# Son_BU_V2.net
KiCad netlist of a schematic drawn in Altium Designer
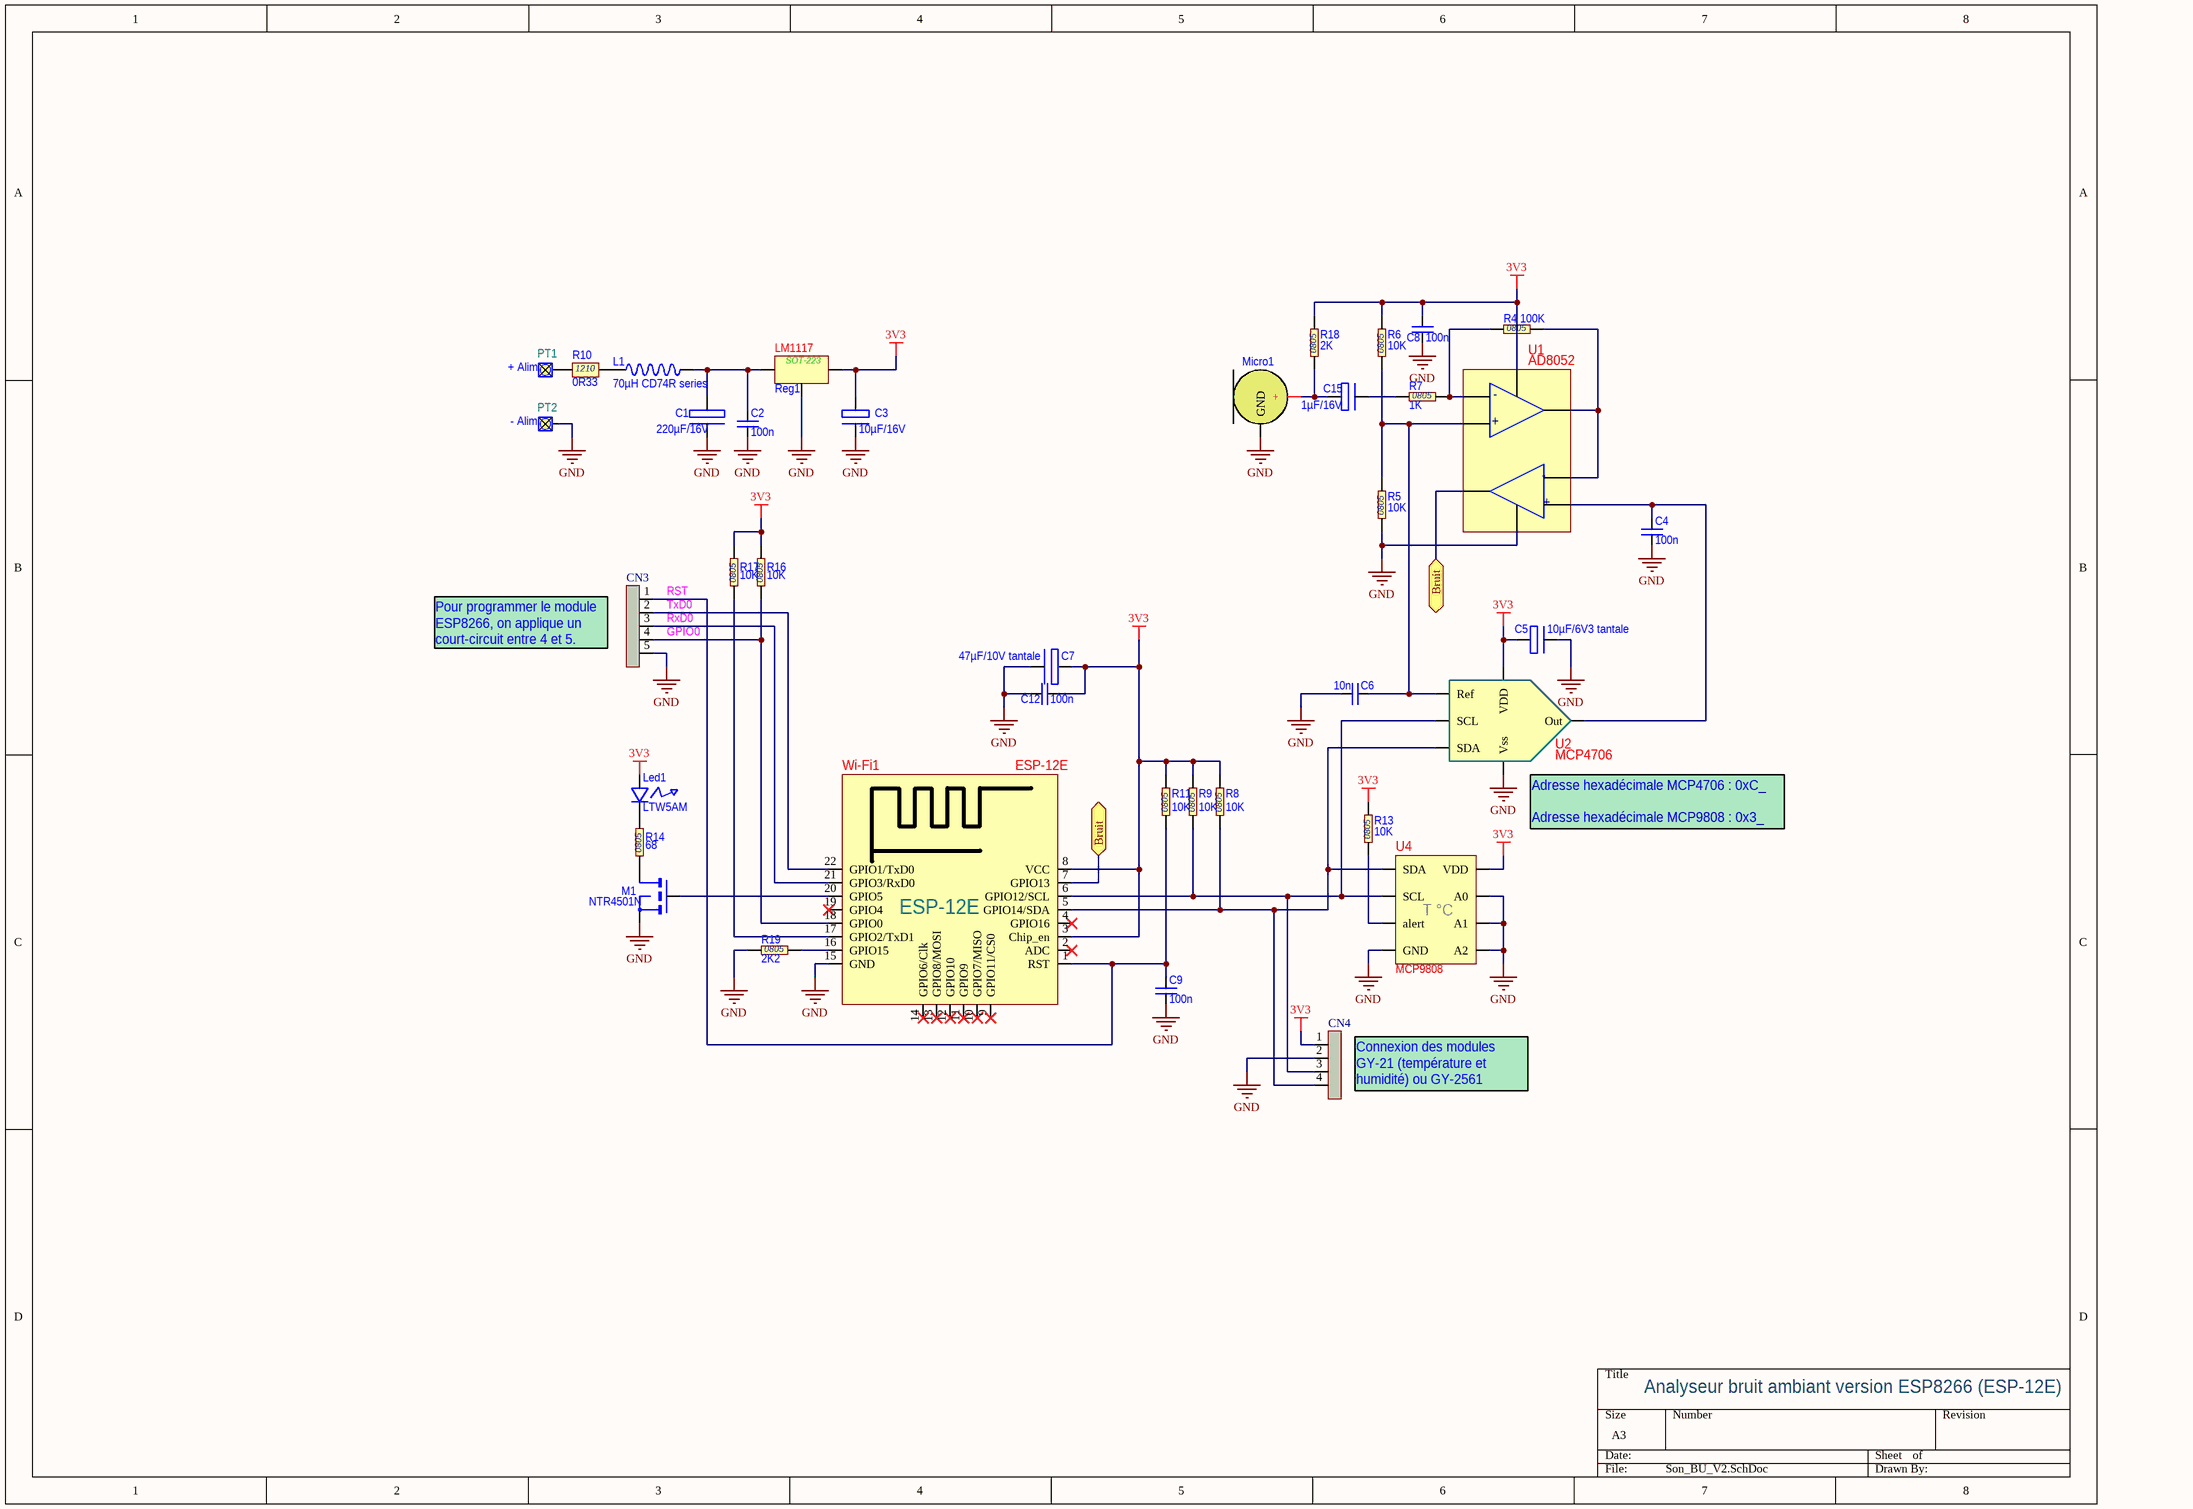
[diagram p0: Son_BU_V2.SchDoc]

(export (version "E")
  (design (tool "Eeschema 10.0.6"))
  (components
    (comp (ref "C1")
      (value "220µF/16V")
      (footprint "7343-31")
      (description "253-5290 case 7343-31")
      (libsource (lib "CMS") (part "tantale 220µF/16V"))
    )
    (comp (ref "C2")
      (value "100n")
      (footprint "0805")
      (description "CMS 0805")
      (libsource (lib "CMS") (part "Cap_CMS_0805"))
    )
    (comp (ref "C3")
      (value "10µF/16V")
      (footprint "Tantale 10µF/16V")
      (description "145-7461 case 3216-18")
      (libsource (lib "CMS") (part "tantale 10µF/16V"))
    )
    (comp (ref "C4")
      (value "100n")
      (footprint "0805")
      (description "CMS 0805")
      (libsource (lib "CMS") (part "Cap_CMS_0805"))
    )
    (comp (ref "C5")
      (value "10µF/6V3 tantale")
      (footprint "Tantale 10µF/6V3")
      (description "175-4041 ou 145-7412 case 3216-18")
      (libsource (lib "CMS") (part "tantale 10µF/6V3"))
    )
    (comp (ref "C6")
      (value "10n")
      (footprint "0805")
      (description "CMS 0805")
      (libsource (lib "CMS") (part "Cap_CMS_0805"))
    )
    (comp (ref "C7")
      (value "47µF/10V tantale")
      (footprint "tantale 47µF/10V")
      (description "175-4168")
      (libsource (lib "CMS") (part "tantale 47µF/10V"))
    )
    (comp (ref "C8")
      (value "100n")
      (footprint "0805")
      (description "CMS 0805")
      (libsource (lib "CMS") (part "Cap_CMS_0805"))
    )
    (comp (ref "C9")
      (value "100n")
      (footprint "0805")
      (description "CMS 0805")
      (libsource (lib "CMS") (part "Cap_CMS_0805"))
    )
    (comp (ref "C12")
      (value "100n")
      (footprint "0805")
      (description "CMS 0805")
      (libsource (lib "CMS") (part "Cap_CMS_0805"))
    )
    (comp (ref "C15")
      (value "1µF/16V")
      (footprint "3216-18")
      (description "145-7406 case 3216-18")
      (libsource (lib "CMS") (part "tantale 1µF/16V"))
    )
    (comp (ref "CN3")
      (value "inch_ligne 1x5")
      (footprint "INCH_1x5_droit")
      (description "Inch_1x5_droit")
      (libsource (lib "Connecteurs Contacts") (part "Inch_1x5_droit"))
    )
    (comp (ref "CN4")
      (value "inch_ligne 1x4")
      (footprint "INCH_1x4_droit")
      (description "Inch_1x4_droit")
      (libsource (lib "Connecteurs Contacts") (part "Inch_1x4_droit"))
    )
    (comp (ref "L1")
      (value "70µH CD74R series")
      (footprint "SELF CD74R")
      (description "SMT CD74R Aliexpress")
      (libsource (lib "CMS") (part "Self CD74R"))
    )
    (comp (ref "Led1")
      (value "LTW5AM")
      (footprint "LTW5AM")
      (description "LED Golden Dragon Plus")
      (libsource (lib "CMS") (part "LTW5AM LED"))
    )
    (comp (ref "M1")
      (value "NTR4501N")
      (footprint "SOT23 (NTR4501)")
      (description "MOSFET canal N")
      (libsource (lib "Transistors Bip Mos IGBT") (part "NTR4501N"))
    )
    (comp (ref "Micro1")
      (value "Electret")
      (footprint "Micro_electret simple")
      (description "Microphone électret")
      (libsource (lib "traversants") (part "Microphone_03"))
    )
    (comp (ref "PT1")
      (value "+ Alim")
      (footprint "Pointe de test")
      (description "pointe de test CI 133-6225")
      (libsource (lib "Connecteurs Contacts") (part "PTEST"))
    )
    (comp (ref "PT2")
      (value "- Alim")
      (footprint "Pointe de test")
      (description "pointe de test CI 133-6225")
      (libsource (lib "Connecteurs Contacts") (part "PTEST"))
    )
    (comp (ref "R4")
      (value "100K")
      (footprint "0805")
      (description "CMS 0805")
      (libsource (lib "") (part "Res CMS 0805_1"))
    )
    (comp (ref "R5")
      (value "10K")
      (footprint "0805")
      (description "CMS 0805")
      (libsource (lib "CMS") (part "Res CMS 0805"))
    )
    (comp (ref "R6")
      (value "10K")
      (footprint "0805")
      (description "CMS 0805")
      (libsource (lib "CMS") (part "Res CMS 0805"))
    )
    (comp (ref "R7")
      (value "1K")
      (footprint "0805")
      (description "CMS 0805")
      (libsource (lib "") (part "Res CMS 0805_1"))
    )
    (comp (ref "R8")
      (value "10K")
      (footprint "0805")
      (description "CMS 0805")
      (libsource (lib "CMS") (part "Res CMS 0805"))
    )
    (comp (ref "R9")
      (value "10K")
      (footprint "0805")
      (description "CMS 0805")
      (libsource (lib "CMS") (part "Res CMS 0805"))
    )
    (comp (ref "R10")
      (value "0R33")
      (footprint "1210")
      (description "CMS 1210")
      (libsource (lib "CMS") (part "Res CMS 1210 ERJ14B"))
    )
    (comp (ref "R11")
      (value "10K")
      (footprint "0805")
      (description "CMS 0805")
      (libsource (lib "CMS") (part "Res CMS 0805"))
    )
    (comp (ref "R13")
      (value "10K")
      (footprint "0805")
      (description "CMS 0805")
      (libsource (lib "CMS") (part "Res CMS 0805"))
    )
    (comp (ref "R14")
      (value "68")
      (footprint "0805")
      (description "CMS 0805")
      (libsource (lib "CMS") (part "Res CMS 0805"))
    )
    (comp (ref "R16")
      (value "10K")
      (footprint "0805")
      (description "CMS 0805")
      (libsource (lib "CMS") (part "Res CMS 0805"))
    )
    (comp (ref "R17")
      (value "10K")
      (footprint "0805")
      (description "CMS 0805")
      (libsource (lib "CMS") (part "Res CMS 0805"))
    )
    (comp (ref "R18")
      (value "2K")
      (footprint "0805")
      (description "CMS 0805")
      (libsource (lib "CMS") (part "Res CMS 0805"))
    )
    (comp (ref "R19")
      (value "2K2")
      (footprint "0805")
      (description "CMS 0805")
      (libsource (lib "") (part "Res CMS 0805_1"))
    )
    (comp (ref "Reg1")
      (value "LM1117")
      (footprint "SOT223")
      (description "Régulateur SOT-223")
      (libsource (lib "Convertisseurs_Régulateurs") (part "LM1117/800mA"))
    )
    (comp (ref "U1")
      (value "AD8052")
      (footprint "SOIC08")
      (description "AOP")
      (libsource (lib "CMS") (part "AD8052"))
    )
    (comp (ref "U2")
      (value "MCP4706")
      (footprint "SOT23-6")
      (description "DAC I2C (RS : 738-7111)")
      (libsource (lib "CMS") (part "MCP4706_1"))
    )
    (comp (ref "U4")
      (value "MCP9808")
      (footprint "MSOP-08")
      (description "Digital temperature Sensor")
      (libsource (lib "CMS") (part "MCP9808"))
    )
    (comp (ref "Wi-Fi1")
      (value "ESP-12E")
      (footprint "ESP-12E")
      (description "ESP-12E module Wi-Fi")
      (libsource (lib "CMS") (part "ESP-12E"))
    )
  )
  (nets
    (net (code "1") (name "/Bruit") (class "Default")
      (node (ref "U1") (pin "7") (pinfunction "out_7") (pintype "passive"))
      (node (ref "Wi-Fi1") (pin "7") (pinfunction "GPIO13_7") (pintype "passive"))
    )
    (net (code "2") (name "/GPIO0") (class "Default")
      (node (ref "CN3") (pin "4") (pintype "passive"))
      (node (ref "R16") (pin "1") (pinfunction "CT1_1") (pintype "passive"))
      (node (ref "Wi-Fi1") (pin "18") (pinfunction "GPIO0_18") (pintype "passive"))
    )
    (net (code "3") (name "/RST") (class "Default")
      (node (ref "C9") (pin "2") (pinfunction "CT2_2") (pintype "passive"))
      (node (ref "CN3") (pin "1") (pintype "passive"))
      (node (ref "R11") (pin "1") (pinfunction "CT1_1") (pintype "passive"))
      (node (ref "Wi-Fi1") (pin "1") (pinfunction "RST_1") (pintype "passive"))
    )
    (net (code "4") (name "/RxD0") (class "Default")
      (node (ref "CN3") (pin "3") (pintype "passive"))
      (node (ref "Wi-Fi1") (pin "21") (pinfunction "GPIO3/RxD0_21") (pintype "passive"))
    )
    (net (code "5") (name "/TxD0") (class "Default")
      (node (ref "CN3") (pin "2") (pintype "passive"))
      (node (ref "Wi-Fi1") (pin "22") (pinfunction "GPIO1/TxD0_22") (pintype "passive"))
    )
    (net (code "6") (name "3V3") (class "Default")
      (node (ref "C12") (pin "2") (pinfunction "CT2_2") (pintype "passive"))
      (node (ref "C3") (pin "1") (pinfunction "V+_1") (pintype "passive"))
      (node (ref "C5") (pin "1") (pinfunction "V+_1") (pintype "passive"))
      (node (ref "C7") (pin "1") (pinfunction "V+_1") (pintype "passive"))
      (node (ref "C8") (pin "2") (pinfunction "CT2_2") (pintype "passive"))
      (node (ref "CN4") (pin "1") (pintype "passive"))
      (node (ref "Led1") (pin "1") (pinfunction "anode_1") (pintype "passive"))
      (node (ref "R11") (pin "2") (pinfunction "CT2_2") (pintype "passive"))
      (node (ref "R13") (pin "2") (pinfunction "CT2_2") (pintype "passive"))
      (node (ref "R16") (pin "2") (pinfunction "CT2_2") (pintype "passive"))
      (node (ref "R17") (pin "2") (pinfunction "CT2_2") (pintype "passive"))
      (node (ref "R18") (pin "2") (pinfunction "CT2_2") (pintype "passive"))
      (node (ref "R6") (pin "2") (pinfunction "CT2_2") (pintype "passive"))
      (node (ref "R8") (pin "2") (pinfunction "CT2_2") (pintype "passive"))
      (node (ref "R9") (pin "2") (pinfunction "CT2_2") (pintype "passive"))
      (node (ref "Reg1") (pin "2") (pinfunction "OUT_2") (pintype "passive"))
      (node (ref "U1") (pin "8") (pinfunction "V+_8") (pintype "passive"))
      (node (ref "U2") (pin "3") (pinfunction "VDD_3") (pintype "passive"))
      (node (ref "U4") (pin "8") (pinfunction "VDD_8") (pintype "passive"))
      (node (ref "Wi-Fi1") (pin "3") (pinfunction "Chip_en_3") (pintype "passive"))
      (node (ref "Wi-Fi1") (pin "8") (pinfunction "VCC_8") (pintype "passive"))
    )
    (net (code "7") (name "GND") (class "Default")
      (node (ref "C1") (pin "2") (pinfunction "V-_2") (pintype "passive"))
      (node (ref "C12") (pin "1") (pinfunction "CT1_1") (pintype "passive"))
      (node (ref "C2") (pin "1") (pinfunction "CT1_1") (pintype "passive"))
      (node (ref "C3") (pin "2") (pinfunction "V-_2") (pintype "passive"))
      (node (ref "C4") (pin "1") (pinfunction "CT1_1") (pintype "passive"))
      (node (ref "C5") (pin "2") (pinfunction "V-_2") (pintype "passive"))
      (node (ref "C6") (pin "2") (pinfunction "CT2_2") (pintype "passive"))
      (node (ref "C7") (pin "2") (pinfunction "V-_2") (pintype "passive"))
      (node (ref "C8") (pin "1") (pinfunction "CT1_1") (pintype "passive"))
      (node (ref "C9") (pin "1") (pinfunction "CT1_1") (pintype "passive"))
      (node (ref "CN3") (pin "5") (pintype "passive"))
      (node (ref "CN4") (pin "2") (pintype "passive"))
      (node (ref "M1") (pin "3") (pinfunction "S_3") (pintype "passive"))
      (node (ref "Micro1") (pin "0") (pinfunction "GND_0") (pintype "passive"))
      (node (ref "PT2") (pin "1") (pinfunction "PIN_1") (pintype "passive"))
      (node (ref "R19") (pin "1") (pinfunction "CT1_1") (pintype "passive"))
      (node (ref "R5") (pin "1") (pinfunction "CT1_1") (pintype "passive"))
      (node (ref "Reg1") (pin "1") (pinfunction "GND_1") (pintype "passive"))
      (node (ref "U1") (pin "4") (pinfunction "V-_4") (pintype "passive"))
      (node (ref "U2") (pin "2") (pinfunction "Vss_2") (pintype "passive"))
      (node (ref "U4") (pin "4") (pinfunction "GND_4") (pintype "passive"))
      (node (ref "U4") (pin "5") (pinfunction "A2_5") (pintype "passive"))
      (node (ref "U4") (pin "6") (pinfunction "A1_6") (pintype "passive"))
      (node (ref "U4") (pin "7") (pinfunction "A0_7") (pintype "passive"))
      (node (ref "Wi-Fi1") (pin "15") (pinfunction "GND_15") (pintype "passive"))
    )
    (net (code "8") (name "Net-(C1-V+)") (class "Default")
      (node (ref "C1") (pin "1") (pinfunction "V+_1") (pintype "passive"))
      (node (ref "C2") (pin "2") (pinfunction "CT2_2") (pintype "passive"))
      (node (ref "L1") (pin "1") (pinfunction "CT1_1") (pintype "passive"))
      (node (ref "Reg1") (pin "3") (pinfunction "IN_3") (pintype "passive"))
    )
    (net (code "9") (name "Net-(C4-CT2)") (class "Default")
      (node (ref "C4") (pin "2") (pinfunction "CT2_2") (pintype "passive"))
      (node (ref "U1") (pin "5") (pinfunction "in+_5") (pintype "passive"))
      (node (ref "U2") (pin "1") (pinfunction "Out_1") (pintype "passive"))
    )
    (net (code "10") (name "Net-(C6-CT1)") (class "Default")
      (node (ref "C6") (pin "1") (pinfunction "CT1_1") (pintype "passive"))
      (node (ref "R5") (pin "2") (pinfunction "CT2_2") (pintype "passive"))
      (node (ref "R6") (pin "1") (pinfunction "CT1_1") (pintype "passive"))
      (node (ref "U1") (pin "3") (pinfunction "in+_3") (pintype "passive"))
      (node (ref "U2") (pin "6") (pinfunction "Ref_6") (pintype "passive"))
    )
    (net (code "11") (name "Net-(C15-V+)") (class "Default")
      (node (ref "C15") (pin "1") (pinfunction "V+_1") (pintype "passive"))
      (node (ref "Micro1") (pin "1") (pinfunction "+_1") (pintype "passive"))
      (node (ref "R18") (pin "1") (pinfunction "CT1_1") (pintype "passive"))
    )
    (net (code "12") (name "Net-(C15-V-)") (class "Default")
      (node (ref "C15") (pin "2") (pinfunction "V-_2") (pintype "passive"))
      (node (ref "R7") (pin "1") (pinfunction "CT1_1") (pintype "passive"))
    )
    (net (code "13") (name "Net-(L1-CT2)") (class "Default")
      (node (ref "L1") (pin "2") (pinfunction "CT2_2") (pintype "passive"))
      (node (ref "R10") (pin "2") (pinfunction "CT2_2") (pintype "passive"))
    )
    (net (code "14") (name "Net-(Led1-cathode)") (class "Default")
      (node (ref "Led1") (pin "2") (pinfunction "cathode_2") (pintype "passive"))
      (node (ref "R14") (pin "2") (pinfunction "CT2_2") (pintype "passive"))
    )
    (net (code "15") (name "Net-(M1-D)") (class "Default")
      (node (ref "M1") (pin "1") (pinfunction "D_1") (pintype "passive"))
      (node (ref "R14") (pin "1") (pinfunction "CT1_1") (pintype "passive"))
    )
    (net (code "16") (name "Net-(M1-G)") (class "Default")
      (node (ref "M1") (pin "2") (pinfunction "G_2") (pintype "passive"))
      (node (ref "Wi-Fi1") (pin "20") (pinfunction "GPIO5_20") (pintype "passive"))
    )
    (net (code "17") (name "Net-(PT1-PIN)") (class "Default")
      (node (ref "PT1") (pin "1") (pinfunction "PIN_1") (pintype "passive"))
      (node (ref "R10") (pin "1") (pinfunction "CT1_1") (pintype "passive"))
    )
    (net (code "18") (name "Net-(R4-CT1)") (class "Default")
      (node (ref "R4") (pin "1") (pinfunction "CT1_1") (pintype "passive"))
      (node (ref "R7") (pin "2") (pinfunction "CT2_2") (pintype "passive"))
      (node (ref "U1") (pin "2") (pinfunction "in-_2") (pintype "passive"))
    )
    (net (code "19") (name "Net-(R4-CT2)") (class "Default")
      (node (ref "R4") (pin "2") (pinfunction "CT2_2") (pintype "passive"))
      (node (ref "U1") (pin "1") (pinfunction "out_1") (pintype "passive"))
      (node (ref "U1") (pin "6") (pinfunction "in-_6") (pintype "passive"))
    )
    (net (code "20") (name "Net-(R8-CT1)") (class "Default")
      (node (ref "CN4") (pin "4") (pintype "passive"))
      (node (ref "R8") (pin "1") (pinfunction "CT1_1") (pintype "passive"))
      (node (ref "U2") (pin "4") (pinfunction "SDA_4") (pintype "passive"))
      (node (ref "U4") (pin "1") (pinfunction "SDA_1") (pintype "passive"))
      (node (ref "Wi-Fi1") (pin "5") (pinfunction "GPIO14/SDA_5") (pintype "passive"))
    )
    (net (code "21") (name "Net-(R9-CT1)") (class "Default")
      (node (ref "CN4") (pin "3") (pintype "passive"))
      (node (ref "R9") (pin "1") (pinfunction "CT1_1") (pintype "passive"))
      (node (ref "U2") (pin "5") (pinfunction "SCL_5") (pintype "passive"))
      (node (ref "U4") (pin "2") (pinfunction "SCL_2") (pintype "passive"))
      (node (ref "Wi-Fi1") (pin "6") (pinfunction "GPIO12/SCL_6") (pintype "passive"))
    )
    (net (code "22") (name "Net-(R13-CT1)") (class "Default")
      (node (ref "R13") (pin "1") (pinfunction "CT1_1") (pintype "passive"))
      (node (ref "U4") (pin "3") (pinfunction "alert_3") (pintype "passive"))
    )
    (net (code "23") (name "Net-(R17-CT1)") (class "Default")
      (node (ref "R17") (pin "1") (pinfunction "CT1_1") (pintype "passive"))
      (node (ref "Wi-Fi1") (pin "17") (pinfunction "GPIO2/TxD1_17") (pintype "passive"))
    )
    (net (code "24") (name "Net-(R19-CT2)") (class "Default")
      (node (ref "R19") (pin "2") (pinfunction "CT2_2") (pintype "passive"))
      (node (ref "Wi-Fi1") (pin "16") (pinfunction "GPIO15_16") (pintype "passive"))
    )
    (net (code "25") (name "unconnected-(Wi-Fi1-ADC-Pad2)") (class "Default")
      (node (ref "Wi-Fi1") (pin "2") (pinfunction "ADC_2") (pintype "passive+no_connect"))
    )
    (net (code "26") (name "unconnected-(Wi-Fi1-GPIO4-Pad19)") (class "Default")
      (node (ref "Wi-Fi1") (pin "19") (pinfunction "GPIO4_19") (pintype "passive+no_connect"))
    )
    (net (code "27") (name "unconnected-(Wi-Fi1-GPIO6{slash}Clk-Pad14)") (class "Default")
      (node (ref "Wi-Fi1") (pin "14") (pinfunction "GPIO6/Clk_14") (pintype "passive+no_connect"))
    )
    (net (code "28") (name "unconnected-(Wi-Fi1-GPIO7{slash}MISO-Pad10)") (class "Default")
      (node (ref "Wi-Fi1") (pin "10") (pinfunction "GPIO7/MISO_10") (pintype "passive+no_connect"))
    )
    (net (code "29") (name "unconnected-(Wi-Fi1-GPIO8{slash}MOSI-Pad13)") (class "Default")
      (node (ref "Wi-Fi1") (pin "13") (pinfunction "GPIO8/MOSI_13") (pintype "passive+no_connect"))
    )
    (net (code "30") (name "unconnected-(Wi-Fi1-GPIO9-Pad11)") (class "Default")
      (node (ref "Wi-Fi1") (pin "11") (pinfunction "GPIO9_11") (pintype "passive+no_connect"))
    )
    (net (code "31") (name "unconnected-(Wi-Fi1-GPIO10-Pad12)") (class "Default")
      (node (ref "Wi-Fi1") (pin "12") (pinfunction "GPIO10_12") (pintype "passive+no_connect"))
    )
    (net (code "32") (name "unconnected-(Wi-Fi1-GPIO11{slash}CS0-Pad9)") (class "Default")
      (node (ref "Wi-Fi1") (pin "9") (pinfunction "GPIO11/CS0_9") (pintype "passive+no_connect"))
    )
    (net (code "33") (name "unconnected-(Wi-Fi1-GPIO16-Pad4)") (class "Default")
      (node (ref "Wi-Fi1") (pin "4") (pinfunction "GPIO16_4") (pintype "passive+no_connect"))
    )
  )
)
